# rapidshark-flywheel-controller-mk-1_0.net
KiCad netlist of a schematic drawn in EAGLE
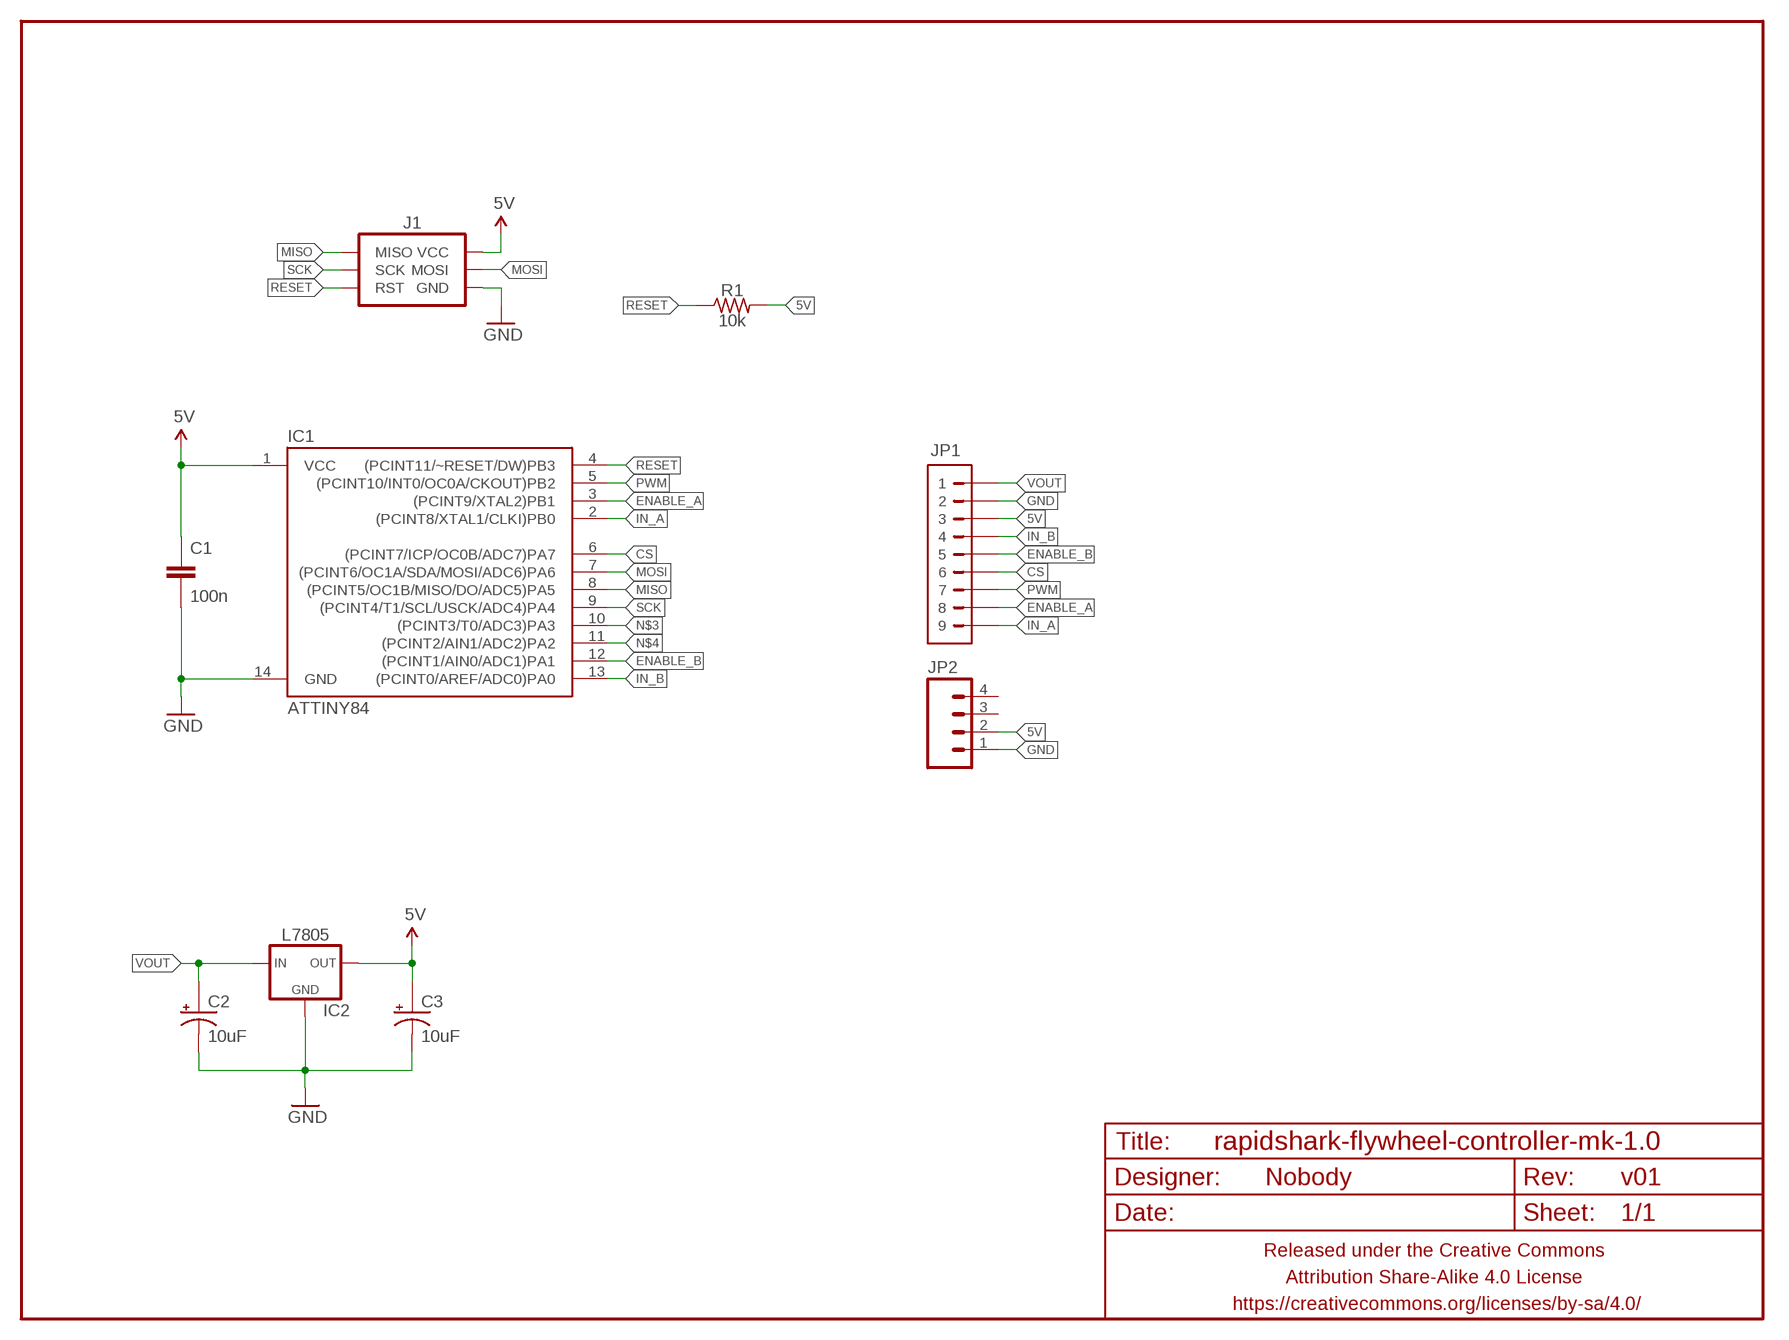
[diagram p0: schematic, sheet 1]

(export (version "E")
  (design (tool "Eeschema 10.0.6"))
  (components
    (comp (ref "C1")
      (value "100n")
      (footprint "eagle-import:C0805")
      (libsource (lib "eagle-import") (part "CAPACITOR-CERAMICC0805"))
    )
    (comp (ref "C2")
      (value "10uF")
      (footprint "eagle-import:E2-5")
      (libsource (lib "eagle-import") (part "CAPACITOR-POLARIZEDE2-5"))
    )
    (comp (ref "C3")
      (value "10uF")
      (footprint "eagle-import:E2-5")
      (libsource (lib "eagle-import") (part "CAPACITOR-POLARIZEDE2-5"))
    )
    (comp (ref "FRAME1")
      (value "FRAME-LETTERNO_PACKAGE")
      (footprint "eagle-import:DUMMY")
      (fields (field (name "DESIGNER") "Nobody"))
      (libsource (lib "eagle-import") (part "FRAME-LETTERNO_PACKAGE"))
    )
    (comp (ref "IC1")
      (value "ATTINY84")
      (footprint "eagle-import:SO14")
      (libsource (lib "eagle-import") (part "ATTINY84"))
    )
    (comp (ref "IC2")
      (value "L7805")
      (footprint "eagle-import:TO-92-AMMO")
      (libsource (lib "eagle-import") (part "V_REG_78XXTO-92-INLINE"))
    )
    (comp (ref "J1")
      (value "AVR_SPI_PRG_6PTH")
      (footprint "eagle-import:2X3")
      (libsource (lib "eagle-import") (part "AVR_SPI_PRG_6PTH"))
    )
    (comp (ref "JP1")
      (value "M09CENTERED")
      (footprint "eagle-import:1X09-CENTERED")
      (libsource (lib "eagle-import") (part "M09CENTERED"))
    )
    (comp (ref "JP2")
      (value "M04JST-PTH-VERT")
      (footprint "eagle-import:JST-4-PH-VERT-PTH")
      (libsource (lib "eagle-import") (part "M04JST-PTH-VERT"))
    )
    (comp (ref "R1")
      (value "10k")
      (footprint "eagle-import:R0805")
      (libsource (lib "eagle-import") (part "RESISTORR0805"))
    )
  )
  (nets
    (net (code "1") (name "5V") (class "Default")
      (node (ref "C1") (pin "1") (pinfunction "1_1") (pintype "passive"))
      (node (ref "C3") (pin "+") (pinfunction "+_+") (pintype "passive"))
      (node (ref "IC1") (pin "1") (pinfunction "VCC_1") (pintype "bidirectional"))
      (node (ref "IC2") (pin "3") (pinfunction "OUT_3") (pintype "bidirectional"))
      (node (ref "J1") (pin "2") (pinfunction "VCC_2") (pintype "passive"))
      (node (ref "JP1") (pin "3") (pinfunction "3_3") (pintype "bidirectional"))
      (node (ref "JP2") (pin "2") (pinfunction "2_2") (pintype "passive"))
      (node (ref "R1") (pin "2") (pinfunction "2_2") (pintype "passive"))
    )
    (net (code "2") (name "CS") (class "Default")
      (node (ref "IC1") (pin "6") (pinfunction "(PCINT7/ICP/OC0B/ADC7)PA7_6") (pintype "bidirectional"))
      (node (ref "JP1") (pin "6") (pinfunction "6_6") (pintype "bidirectional"))
    )
    (net (code "3") (name "ENABLE_A") (class "Default")
      (node (ref "IC1") (pin "3") (pinfunction "(PCINT9/XTAL2)PB1_3") (pintype "bidirectional"))
      (node (ref "JP1") (pin "8") (pinfunction "8_8") (pintype "bidirectional"))
    )
    (net (code "4") (name "ENABLE_B") (class "Default")
      (node (ref "IC1") (pin "12") (pinfunction "(PCINT1/AIN0/ADC1)PA1_12") (pintype "bidirectional"))
      (node (ref "JP1") (pin "5") (pinfunction "5_5") (pintype "bidirectional"))
    )
    (net (code "5") (name "GND") (class "Default")
      (node (ref "C1") (pin "2") (pinfunction "2_2") (pintype "passive"))
      (node (ref "C2") (pin "-") (pinfunction "-_-") (pintype "passive"))
      (node (ref "C3") (pin "-") (pinfunction "-_-") (pintype "passive"))
      (node (ref "IC1") (pin "14") (pinfunction "GND_14") (pintype "bidirectional"))
      (node (ref "IC2") (pin "2") (pinfunction "GND_2") (pintype "bidirectional"))
      (node (ref "J1") (pin "6") (pinfunction "GND_6") (pintype "passive"))
      (node (ref "JP1") (pin "2") (pinfunction "2_2") (pintype "bidirectional"))
      (node (ref "JP2") (pin "1") (pinfunction "1_1") (pintype "passive"))
    )
    (net (code "6") (name "IN_A") (class "Default")
      (node (ref "IC1") (pin "2") (pinfunction "(PCINT8/XTAL1/CLKI)PB0_2") (pintype "bidirectional"))
      (node (ref "JP1") (pin "9") (pinfunction "9_9") (pintype "bidirectional"))
    )
    (net (code "7") (name "IN_B") (class "Default")
      (node (ref "IC1") (pin "13") (pinfunction "(PCINT0/AREF/ADC0)PA0_13") (pintype "bidirectional"))
      (node (ref "JP1") (pin "4") (pinfunction "4_4") (pintype "bidirectional"))
    )
    (net (code "8") (name "MISO") (class "Default")
      (node (ref "IC1") (pin "8") (pinfunction "(PCINT5/OC1B/MISO/DO/ADC5)PA5_8") (pintype "bidirectional"))
      (node (ref "J1") (pin "1") (pinfunction "MISO_1") (pintype "passive"))
    )
    (net (code "9") (name "MOSI") (class "Default")
      (node (ref "IC1") (pin "7") (pinfunction "(PCINT6/OC1A/SDA/MOSI/ADC6)PA6_7") (pintype "bidirectional"))
      (node (ref "J1") (pin "4") (pinfunction "MOSI_4") (pintype "passive"))
    )
    (net (code "10") (name "N$3") (class "Default")
      (node (ref "IC1") (pin "10") (pinfunction "(PCINT3/T0/ADC3)PA3_10") (pintype "bidirectional"))
    )
    (net (code "11") (name "N$4") (class "Default")
      (node (ref "IC1") (pin "11") (pinfunction "(PCINT2/AIN1/ADC2)PA2_11") (pintype "bidirectional"))
    )
    (net (code "12") (name "PWM") (class "Default")
      (node (ref "IC1") (pin "5") (pinfunction "(PCINT10/INT0/OC0A/CKOUT)PB2_5") (pintype "bidirectional"))
      (node (ref "JP1") (pin "7") (pinfunction "7_7") (pintype "bidirectional"))
    )
    (net (code "13") (name "RESET") (class "Default")
      (node (ref "IC1") (pin "4") (pinfunction "(PCINT11/~{RESET/DW})PB3_4") (pintype "bidirectional"))
      (node (ref "J1") (pin "5") (pinfunction "RST_5") (pintype "passive"))
      (node (ref "R1") (pin "1") (pinfunction "1_1") (pintype "passive"))
    )
    (net (code "14") (name "SCK") (class "Default")
      (node (ref "IC1") (pin "9") (pinfunction "(PCINT4/T1/SCL/USCK/ADC4)PA4_9") (pintype "bidirectional"))
      (node (ref "J1") (pin "3") (pinfunction "SCK_3") (pintype "passive"))
    )
    (net (code "15") (name "VOUT") (class "Default")
      (node (ref "C2") (pin "+") (pinfunction "+_+") (pintype "passive"))
      (node (ref "IC2") (pin "1") (pinfunction "IN_1") (pintype "bidirectional"))
      (node (ref "JP1") (pin "1") (pinfunction "1_1") (pintype "bidirectional"))
    )
    (net (code "16") (name "unconnected-(JP2-Pad3)") (class "Default")
      (node (ref "JP2") (pin "3") (pinfunction "3_3") (pintype "passive"))
    )
    (net (code "17") (name "unconnected-(JP2-Pad4)") (class "Default")
      (node (ref "JP2") (pin "4") (pinfunction "4_4") (pintype "passive"))
    )
  )
)
